# tC-mcu-adapter-rev1.net
KiCad netlist of a schematic drawn in EAGLE
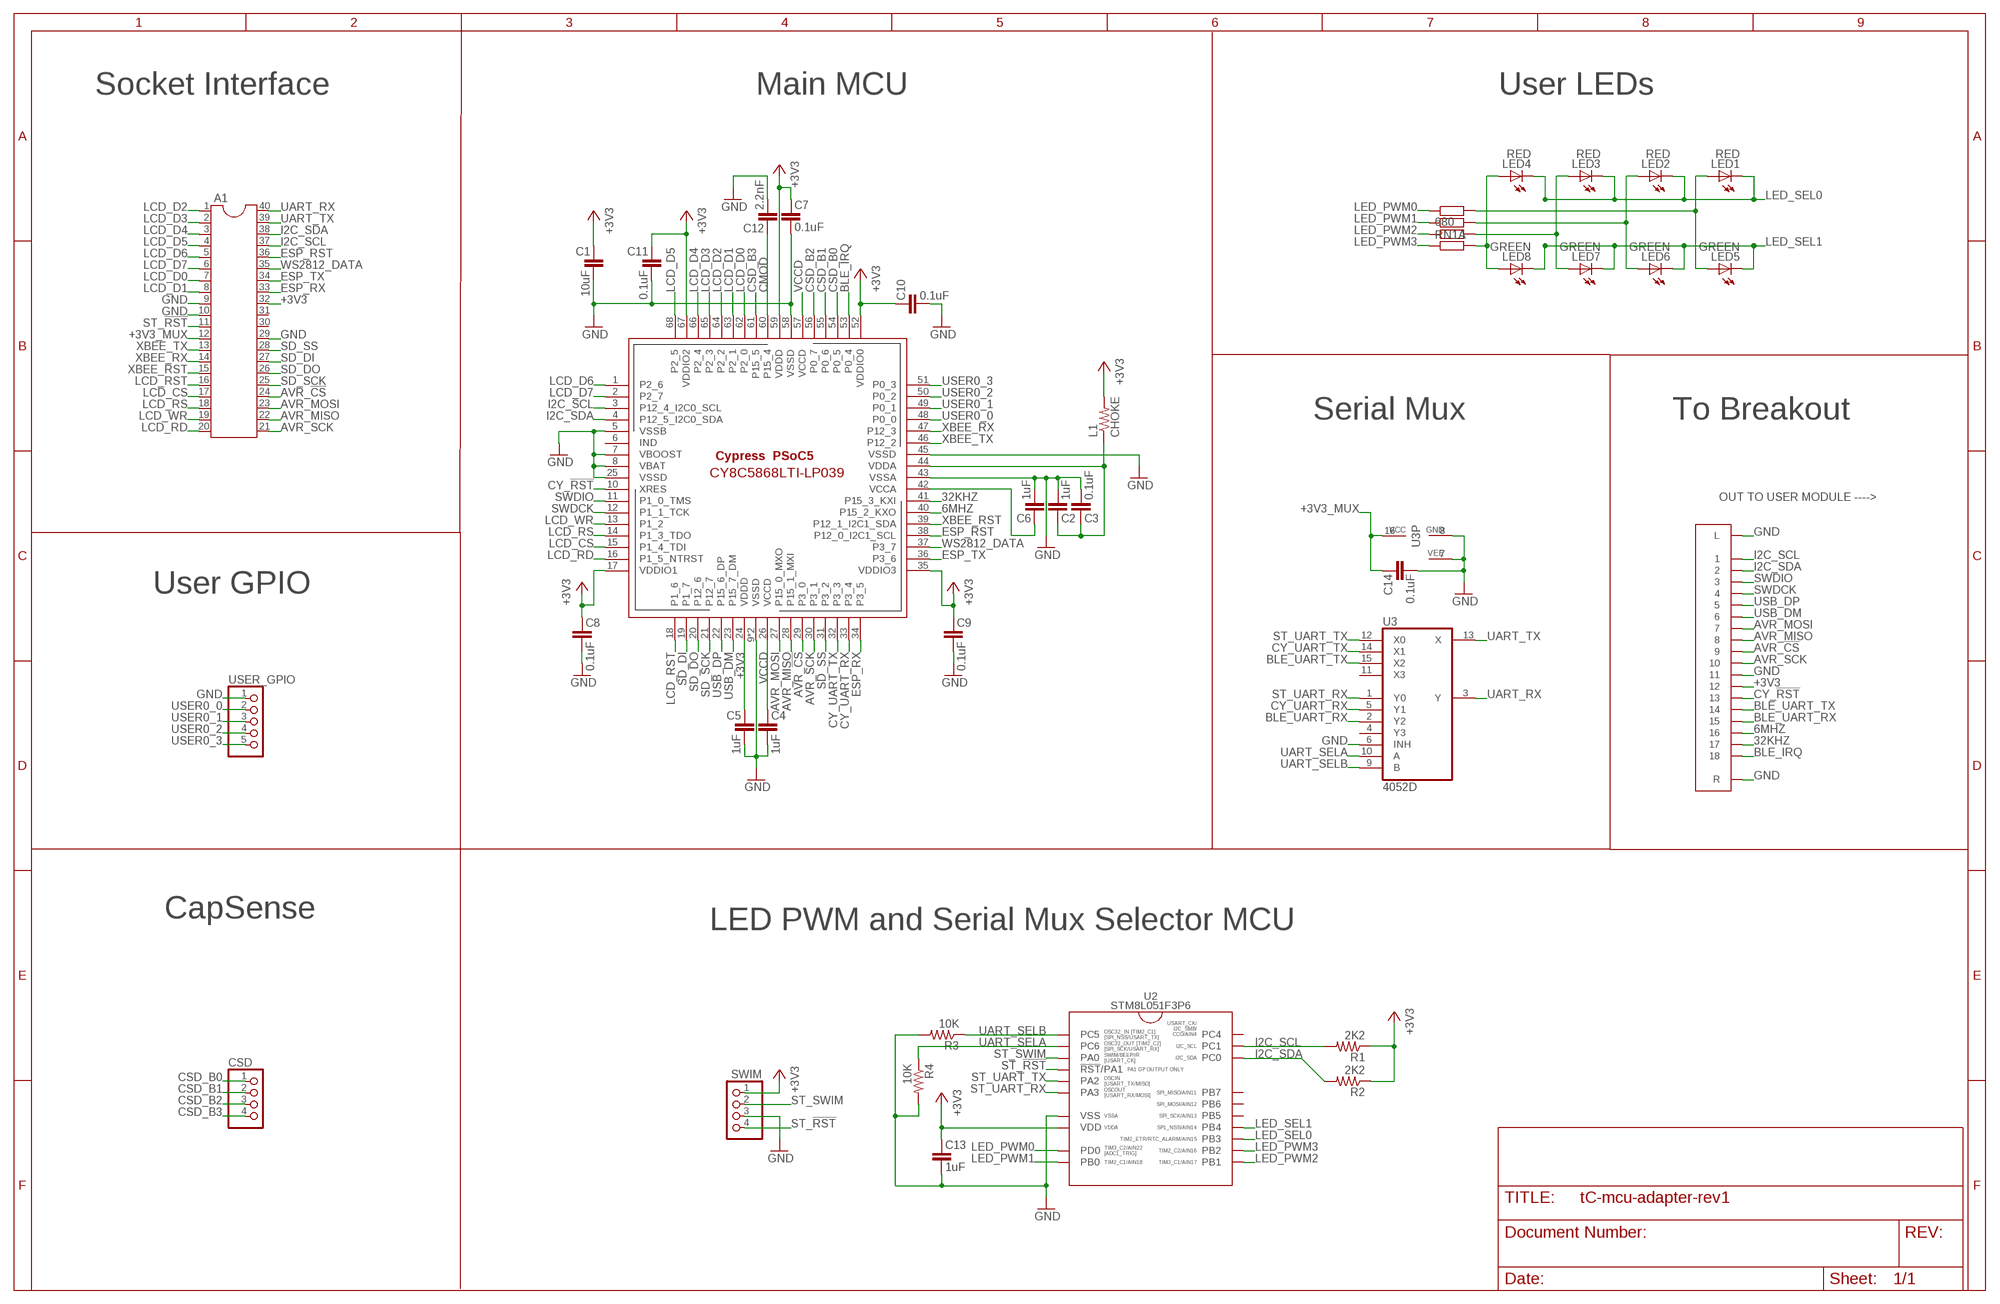
[diagram p0: schematic, sheet 1]

(export (version "E")
  (design (tool "Eeschema 10.0.6"))
  (components
    (comp (ref "A1")
      (value "DIL40")
      (footprint "eagle-import:DIL40")
      (libsource (lib "eagle-import") (part "DIL40"))
    )
    (comp (ref "C1")
      (value "10uF")
      (footprint "eagle-import:C0805K")
      (libsource (lib "eagle-import") (part "C-EUC0805K"))
    )
    (comp (ref "C2")
      (value "1uF")
      (footprint "eagle-import:C0603K")
      (libsource (lib "eagle-import") (part "C-EUC0603K"))
    )
    (comp (ref "C3")
      (value "0.1uF")
      (footprint "eagle-import:C0603K")
      (libsource (lib "eagle-import") (part "C-EUC0603K"))
    )
    (comp (ref "C4")
      (value "1uF")
      (footprint "eagle-import:C0603K")
      (libsource (lib "eagle-import") (part "C-EUC0603K"))
    )
    (comp (ref "C5")
      (value "1uF")
      (footprint "eagle-import:C0603K")
      (libsource (lib "eagle-import") (part "C-EUC0603K"))
    )
    (comp (ref "C6")
      (value "1uF")
      (footprint "eagle-import:C0603K")
      (libsource (lib "eagle-import") (part "C-EUC0603K"))
    )
    (comp (ref "C7")
      (value "0.1uF")
      (footprint "eagle-import:C0603K")
      (libsource (lib "eagle-import") (part "C-EUC0603K"))
    )
    (comp (ref "C8")
      (value "0.1uF")
      (footprint "eagle-import:C0603K")
      (libsource (lib "eagle-import") (part "C-EUC0603K"))
    )
    (comp (ref "C9")
      (value "0.1uF")
      (footprint "eagle-import:C0603K")
      (libsource (lib "eagle-import") (part "C-EUC0603K"))
    )
    (comp (ref "C10")
      (value "0.1uF")
      (footprint "eagle-import:C0603K")
      (libsource (lib "eagle-import") (part "C-EUC0603K"))
    )
    (comp (ref "C11")
      (value "0.1uF")
      (footprint "eagle-import:C0603K")
      (libsource (lib "eagle-import") (part "C-EUC0603K"))
    )
    (comp (ref "C12")
      (value "2.2nF")
      (footprint "eagle-import:C0603K")
      (libsource (lib "eagle-import") (part "C-EUC0603K"))
    )
    (comp (ref "C13")
      (value "1uF")
      (footprint "eagle-import:C0402K")
      (libsource (lib "eagle-import") (part "C-EUC0402K"))
    )
    (comp (ref "C14")
      (value "0.1uF")
      (footprint "eagle-import:C0402K")
      (libsource (lib "eagle-import") (part "C-EUC0402K"))
    )
    (comp (ref "CN1")
      (value "FPC_CONN_18PIN_0.5MM_SMT")
      (footprint "eagle-import:FPC_CONN_18PIN_0.5MM_SMT")
      (libsource (lib "eagle-import") (part "FPC_CONN_18PIN_0.5MM_SMT"))
    )
    (comp (ref "CSD")
      (value "CAP_INTERCONNECT")
      (footprint "eagle-import:CAP_INTERCONNECT")
      (libsource (lib "eagle-import") (part "CAP_INTERCONNECT"))
    )
    (comp (ref "L1")
      (value "CHOKE")
      (footprint "eagle-import:R0805")
      (libsource (lib "eagle-import") (part "R-US_R0805"))
    )
    (comp (ref "LED1")
      (value "RED")
      (footprint "eagle-import:LED-805")
      (libsource (lib "eagle-import") (part "LED-0805"))
    )
    (comp (ref "LED2")
      (value "RED")
      (footprint "eagle-import:LED-805")
      (libsource (lib "eagle-import") (part "LED-0805"))
    )
    (comp (ref "LED3")
      (value "RED")
      (footprint "eagle-import:LED-805")
      (libsource (lib "eagle-import") (part "LED-0805"))
    )
    (comp (ref "LED4")
      (value "RED")
      (footprint "eagle-import:LED-805")
      (libsource (lib "eagle-import") (part "LED-0805"))
    )
    (comp (ref "LED5")
      (value "GREEN")
      (footprint "eagle-import:LED-805")
      (libsource (lib "eagle-import") (part "LED-0805"))
    )
    (comp (ref "LED6")
      (value "GREEN")
      (footprint "eagle-import:LED-805")
      (libsource (lib "eagle-import") (part "LED-0805"))
    )
    (comp (ref "LED7")
      (value "GREEN")
      (footprint "eagle-import:LED-805")
      (libsource (lib "eagle-import") (part "LED-0805"))
    )
    (comp (ref "LED8")
      (value "GREEN")
      (footprint "eagle-import:LED-805")
      (libsource (lib "eagle-import") (part "LED-0805"))
    )
    (comp (ref "R1")
      (value "2K2")
      (footprint "eagle-import:R0603")
      (libsource (lib "eagle-import") (part "R-US_R0603"))
    )
    (comp (ref "R2")
      (value "2K2")
      (footprint "eagle-import:R0603")
      (libsource (lib "eagle-import") (part "R-US_R0603"))
    )
    (comp (ref "R3")
      (value "10K")
      (footprint "eagle-import:R0603")
      (libsource (lib "eagle-import") (part "R-US_R0603"))
    )
    (comp (ref "R4")
      (value "10K")
      (footprint "eagle-import:R0603")
      (libsource (lib "eagle-import") (part "R-US_R0603"))
    )
    (comp (ref "RN1")
      (value "680")
      (footprint "eagle-import:RN8P-4R-CRA06S")
      (libsource (lib "eagle-import") (part "RESISTOR_ARRAY_4"))
    )
    (comp (ref "SWIM")
      (value "PINHD-1X4")
      (footprint "eagle-import:1X04")
      (libsource (lib "eagle-import") (part "PINHD-1X4"))
    )
    (comp (ref "U1")
      (value "CY8C5XXX-68-N")
      (footprint "eagle-import:QFN68N")
      (libsource (lib "eagle-import") (part "CY8C5XXX-68-N"))
    )
    (comp (ref "U2")
      (value "STM8L051F3P6")
      (footprint "eagle-import:TSSOP20")
      (libsource (lib "eagle-import") (part "STM8L051F3P6"))
    )
    (comp (ref "U3")
      (value "4052D")
      (footprint "eagle-import:SO16")
      (libsource (lib "eagle-import") (part "4052D"))
    )
    (comp (ref "USER_GPIO")
      (value "PINHD-1X5/90")
      (footprint "eagle-import:1X05_90")
      (libsource (lib "eagle-import") (part "PINHD-1X5/90"))
    )
  )
  (nets
    (net (code "1") (name "+3V3") (class "Default")
      (node (ref "A1") (pin "32") (pinfunction "32_32") (pintype "passive"))
      (node (ref "C1") (pin "1") (pinfunction "1_1") (pintype "passive"))
      (node (ref "C10") (pin "1") (pinfunction "1_1") (pintype "passive"))
      (node (ref "C11") (pin "1") (pinfunction "1_1") (pintype "passive"))
      (node (ref "C13") (pin "1") (pinfunction "1_1") (pintype "passive"))
      (node (ref "C5") (pin "1") (pinfunction "1_1") (pintype "passive"))
      (node (ref "C7") (pin "1") (pinfunction "1_1") (pintype "passive"))
      (node (ref "C8") (pin "1") (pinfunction "1_1") (pintype "passive"))
      (node (ref "C9") (pin "1") (pinfunction "1_1") (pintype "passive"))
      (node (ref "CN1") (pin "12") (pinfunction "12_12") (pintype "bidirectional"))
      (node (ref "L1") (pin "2") (pinfunction "2_2") (pintype "passive"))
      (node (ref "R1") (pin "1") (pinfunction "1_1") (pintype "passive"))
      (node (ref "R2") (pin "1") (pinfunction "1_1") (pintype "passive"))
      (node (ref "SWIM") (pin "1") (pinfunction "1_1") (pintype "passive"))
      (node (ref "U1") (pin "17") (pinfunction "VDDIO1_17") (pintype "passive"))
      (node (ref "U1") (pin "24") (pinfunction "VDDD_24") (pintype "passive"))
      (node (ref "U1") (pin "35") (pinfunction "VDDIO3_35") (pintype "passive"))
      (node (ref "U1") (pin "52") (pinfunction "VDDIO0_52") (pintype "passive"))
      (node (ref "U1") (pin "59") (pinfunction "VDDD_59") (pintype "passive"))
      (node (ref "U1") (pin "67") (pinfunction "VDDIO2_67") (pintype "passive"))
      (node (ref "U2") (pin "8") (pinfunction "VDD_8") (pintype "bidirectional"))
    )
    (net (code "2") (name "/+3V3_MUX") (class "Default")
      (node (ref "A1") (pin "12") (pinfunction "12_12") (pintype "passive"))
      (node (ref "C14") (pin "1") (pinfunction "1_1") (pintype "passive"))
      (node (ref "U3") (pin "16") (pinfunction "VCC_16") (pintype "power_in"))
    )
    (net (code "3") (name "/6MHZ") (class "Default")
      (node (ref "CN1") (pin "16") (pinfunction "16_16") (pintype "bidirectional"))
      (node (ref "U1") (pin "40") (pinfunction "P15_2_KXO_40") (pintype "passive"))
    )
    (net (code "4") (name "/32KHZ") (class "Default")
      (node (ref "CN1") (pin "17") (pinfunction "17_17") (pintype "bidirectional"))
      (node (ref "U1") (pin "41") (pinfunction "P15_3_KXI_41") (pintype "passive"))
    )
    (net (code "5") (name "/AVR_MISO") (class "Default")
      (node (ref "A1") (pin "22") (pinfunction "22_22") (pintype "passive"))
      (node (ref "CN1") (pin "8") (pinfunction "8_8") (pintype "bidirectional"))
      (node (ref "U1") (pin "28") (pinfunction "P15_1_MXI_28") (pintype "passive"))
    )
    (net (code "6") (name "/AVR_MOSI") (class "Default")
      (node (ref "A1") (pin "23") (pinfunction "23_23") (pintype "passive"))
      (node (ref "CN1") (pin "7") (pinfunction "7_7") (pintype "bidirectional"))
      (node (ref "U1") (pin "27") (pinfunction "P15_0_MXO_27") (pintype "passive"))
    )
    (net (code "7") (name "/AVR_SCK") (class "Default")
      (node (ref "A1") (pin "21") (pinfunction "21_21") (pintype "passive"))
      (node (ref "CN1") (pin "10") (pinfunction "10_10") (pintype "bidirectional"))
      (node (ref "U1") (pin "30") (pinfunction "P3_1_30") (pintype "passive"))
    )
    (net (code "8") (name "/AVR_~{CS}") (class "Default")
      (node (ref "A1") (pin "24") (pinfunction "24_24") (pintype "passive"))
      (node (ref "CN1") (pin "9") (pinfunction "9_9") (pintype "bidirectional"))
      (node (ref "U1") (pin "29") (pinfunction "P3_0_29") (pintype "passive"))
    )
    (net (code "9") (name "/BLE_IRQ") (class "Default")
      (node (ref "CN1") (pin "18") (pinfunction "18_18") (pintype "bidirectional"))
      (node (ref "U1") (pin "53") (pinfunction "P0_4_53") (pintype "passive"))
    )
    (net (code "10") (name "/BLE_UART_RX") (class "Default")
      (node (ref "CN1") (pin "15") (pinfunction "15_15") (pintype "bidirectional"))
      (node (ref "U3") (pin "2") (pinfunction "Y2_2") (pintype "bidirectional"))
    )
    (net (code "11") (name "/BLE_UART_TX") (class "Default")
      (node (ref "CN1") (pin "14") (pinfunction "14_14") (pintype "bidirectional"))
      (node (ref "U3") (pin "15") (pinfunction "X2_15") (pintype "bidirectional"))
    )
    (net (code "12") (name "/CMOD") (class "Default")
      (node (ref "C12") (pin "1") (pinfunction "1_1") (pintype "passive"))
      (node (ref "U1") (pin "60") (pinfunction "P15_4_60") (pintype "passive"))
    )
    (net (code "13") (name "/CSD_B0") (class "Default")
      (node (ref "CSD") (pin "1") (pinfunction "1_1") (pintype "passive"))
      (node (ref "U1") (pin "54") (pinfunction "P0_5_54") (pintype "passive"))
    )
    (net (code "14") (name "/CSD_B1") (class "Default")
      (node (ref "CSD") (pin "2") (pinfunction "2_2") (pintype "passive"))
      (node (ref "U1") (pin "55") (pinfunction "P0_6_55") (pintype "passive"))
    )
    (net (code "15") (name "/CSD_B2") (class "Default")
      (node (ref "CSD") (pin "3") (pinfunction "3_3") (pintype "passive"))
      (node (ref "U1") (pin "56") (pinfunction "P0_7_56") (pintype "passive"))
    )
    (net (code "16") (name "/CSD_B3") (class "Default")
      (node (ref "CSD") (pin "4") (pinfunction "4_4") (pintype "passive"))
      (node (ref "U1") (pin "61") (pinfunction "P15_5_61") (pintype "passive"))
    )
    (net (code "17") (name "/CY_UART_RX") (class "Default")
      (node (ref "U1") (pin "33") (pinfunction "P3_4_33") (pintype "passive"))
      (node (ref "U3") (pin "5") (pinfunction "Y1_5") (pintype "bidirectional"))
    )
    (net (code "18") (name "/CY_UART_TX") (class "Default")
      (node (ref "U1") (pin "32") (pinfunction "P3_3_32") (pintype "passive"))
      (node (ref "U3") (pin "14") (pinfunction "X1_14") (pintype "bidirectional"))
    )
    (net (code "19") (name "/CY_~{RST}") (class "Default")
      (node (ref "CN1") (pin "13") (pinfunction "13_13") (pintype "bidirectional"))
      (node (ref "U1") (pin "10") (pinfunction "XRES_10") (pintype "passive"))
    )
    (net (code "20") (name "/ESP_RST") (class "Default")
      (node (ref "A1") (pin "36") (pinfunction "36_36") (pintype "passive"))
      (node (ref "U1") (pin "38") (pinfunction "P12_0_I2C1_SCL_38") (pintype "passive"))
    )
    (net (code "21") (name "/ESP_RX") (class "Default")
      (node (ref "A1") (pin "33") (pinfunction "33_33") (pintype "passive"))
      (node (ref "U1") (pin "34") (pinfunction "P3_5_34") (pintype "passive"))
    )
    (net (code "22") (name "/ESP_TX") (class "Default")
      (node (ref "A1") (pin "34") (pinfunction "34_34") (pintype "passive"))
      (node (ref "U1") (pin "36") (pinfunction "P3_6_36") (pintype "passive"))
    )
    (net (code "23") (name "/I2C_SCL") (class "Default")
      (node (ref "A1") (pin "37") (pinfunction "37_37") (pintype "passive"))
      (node (ref "CN1") (pin "1") (pinfunction "1_1") (pintype "bidirectional"))
      (node (ref "R1") (pin "2") (pinfunction "2_2") (pintype "passive"))
      (node (ref "U1") (pin "3") (pinfunction "P12_4_I2C0_SCL_3") (pintype "passive"))
      (node (ref "U2") (pin "19") (pinfunction "PC1_19") (pintype "bidirectional"))
    )
    (net (code "24") (name "/I2C_SDA") (class "Default")
      (node (ref "A1") (pin "38") (pinfunction "38_38") (pintype "passive"))
      (node (ref "CN1") (pin "2") (pinfunction "2_2") (pintype "bidirectional"))
      (node (ref "R2") (pin "2") (pinfunction "2_2") (pintype "passive"))
      (node (ref "U1") (pin "4") (pinfunction "P12_5_I2C0_SDA_4") (pintype "passive"))
      (node (ref "U2") (pin "18") (pinfunction "PC0_18") (pintype "bidirectional"))
    )
    (net (code "25") (name "/LCD_CS") (class "Default")
      (node (ref "A1") (pin "17") (pinfunction "17_17") (pintype "passive"))
      (node (ref "U1") (pin "15") (pinfunction "P1_4_TDI_15") (pintype "passive"))
    )
    (net (code "26") (name "/LCD_D0") (class "Default")
      (node (ref "A1") (pin "7") (pinfunction "7_7") (pintype "passive"))
      (node (ref "U1") (pin "62") (pinfunction "P2_0_62") (pintype "passive"))
    )
    (net (code "27") (name "/LCD_D1") (class "Default")
      (node (ref "A1") (pin "8") (pinfunction "8_8") (pintype "passive"))
      (node (ref "U1") (pin "63") (pinfunction "P2_1_63") (pintype "passive"))
    )
    (net (code "28") (name "/LCD_D2") (class "Default")
      (node (ref "A1") (pin "1") (pinfunction "1_1") (pintype "passive"))
      (node (ref "U1") (pin "64") (pinfunction "P2_2_64") (pintype "passive"))
    )
    (net (code "29") (name "/LCD_D3") (class "Default")
      (node (ref "A1") (pin "2") (pinfunction "2_2") (pintype "passive"))
      (node (ref "U1") (pin "65") (pinfunction "P2_3_65") (pintype "passive"))
    )
    (net (code "30") (name "/LCD_D4") (class "Default")
      (node (ref "A1") (pin "3") (pinfunction "3_3") (pintype "passive"))
      (node (ref "U1") (pin "66") (pinfunction "P2_4_66") (pintype "passive"))
    )
    (net (code "31") (name "/LCD_D5") (class "Default")
      (node (ref "A1") (pin "4") (pinfunction "4_4") (pintype "passive"))
      (node (ref "U1") (pin "68") (pinfunction "P2_5_68") (pintype "passive"))
    )
    (net (code "32") (name "/LCD_D6") (class "Default")
      (node (ref "A1") (pin "5") (pinfunction "5_5") (pintype "passive"))
      (node (ref "U1") (pin "1") (pinfunction "P2_6_1") (pintype "passive"))
    )
    (net (code "33") (name "/LCD_D7") (class "Default")
      (node (ref "A1") (pin "6") (pinfunction "6_6") (pintype "passive"))
      (node (ref "U1") (pin "2") (pinfunction "P2_7_2") (pintype "passive"))
    )
    (net (code "34") (name "/LCD_RD") (class "Default")
      (node (ref "A1") (pin "20") (pinfunction "20_20") (pintype "passive"))
      (node (ref "U1") (pin "16") (pinfunction "P1_5_NTRST_16") (pintype "passive"))
    )
    (net (code "35") (name "/LCD_RS") (class "Default")
      (node (ref "A1") (pin "18") (pinfunction "18_18") (pintype "passive"))
      (node (ref "U1") (pin "14") (pinfunction "P1_3_TDO_14") (pintype "passive"))
    )
    (net (code "36") (name "/LCD_RST") (class "Default")
      (node (ref "A1") (pin "16") (pinfunction "16_16") (pintype "passive"))
      (node (ref "U1") (pin "18") (pinfunction "P1_6_18") (pintype "passive"))
    )
    (net (code "37") (name "/LCD_WR") (class "Default")
      (node (ref "A1") (pin "19") (pinfunction "19_19") (pintype "passive"))
      (node (ref "U1") (pin "13") (pinfunction "P1_2_13") (pintype "passive"))
    )
    (net (code "38") (name "/LED_PWM0") (class "Default")
      (node (ref "RN1") (pin "4") (pinfunction "1_4") (pintype "passive"))
      (node (ref "U2") (pin "9") (pinfunction "PD0_9") (pintype "bidirectional"))
    )
    (net (code "39") (name "/LED_PWM1") (class "Default")
      (node (ref "RN1") (pin "3") (pinfunction "1_3") (pintype "passive"))
      (node (ref "U2") (pin "10") (pinfunction "PB0_10") (pintype "bidirectional"))
    )
    (net (code "40") (name "/LED_PWM2") (class "Default")
      (node (ref "RN1") (pin "2") (pinfunction "1_2") (pintype "passive"))
      (node (ref "U2") (pin "11") (pinfunction "PB1_11") (pintype "bidirectional"))
    )
    (net (code "41") (name "/LED_PWM3") (class "Default")
      (node (ref "RN1") (pin "1") (pinfunction "1_1") (pintype "passive"))
      (node (ref "U2") (pin "12") (pinfunction "PB2_12") (pintype "bidirectional"))
    )
    (net (code "42") (name "/LED_SEL0") (class "Default")
      (node (ref "LED1") (pin "C") (pinfunction "C_C") (pintype "passive"))
      (node (ref "LED2") (pin "C") (pinfunction "C_C") (pintype "passive"))
      (node (ref "LED3") (pin "C") (pinfunction "C_C") (pintype "passive"))
      (node (ref "LED4") (pin "C") (pinfunction "C_C") (pintype "passive"))
      (node (ref "U2") (pin "13") (pinfunction "PB3_13") (pintype "bidirectional"))
    )
    (net (code "43") (name "/LED_SEL1") (class "Default")
      (node (ref "LED5") (pin "C") (pinfunction "C_C") (pintype "passive"))
      (node (ref "LED6") (pin "C") (pinfunction "C_C") (pintype "passive"))
      (node (ref "LED7") (pin "C") (pinfunction "C_C") (pintype "passive"))
      (node (ref "LED8") (pin "C") (pinfunction "C_C") (pintype "passive"))
      (node (ref "U2") (pin "14") (pinfunction "PB4_14") (pintype "bidirectional"))
    )
    (net (code "44") (name "/SD_DI") (class "Default")
      (node (ref "A1") (pin "27") (pinfunction "27_27") (pintype "passive"))
      (node (ref "U1") (pin "19") (pinfunction "P1_7_19") (pintype "passive"))
    )
    (net (code "45") (name "/SD_DO") (class "Default")
      (node (ref "A1") (pin "26") (pinfunction "26_26") (pintype "passive"))
      (node (ref "U1") (pin "20") (pinfunction "P12_6_20") (pintype "passive"))
    )
    (net (code "46") (name "/SD_SCK") (class "Default")
      (node (ref "A1") (pin "25") (pinfunction "25_25") (pintype "passive"))
      (node (ref "U1") (pin "21") (pinfunction "P12_7_21") (pintype "passive"))
    )
    (net (code "47") (name "/SD_SS") (class "Default")
      (node (ref "A1") (pin "28") (pinfunction "28_28") (pintype "passive"))
      (node (ref "U1") (pin "31") (pinfunction "P3_2_31") (pintype "passive"))
    )
    (net (code "48") (name "/ST_SWIM") (class "Default")
      (node (ref "SWIM") (pin "2") (pinfunction "2_2") (pintype "passive"))
      (node (ref "U2") (pin "3") (pinfunction "PA0_3") (pintype "bidirectional"))
    )
    (net (code "49") (name "/ST_UART_RX") (class "Default")
      (node (ref "U2") (pin "6") (pinfunction "PA3_6") (pintype "bidirectional"))
      (node (ref "U3") (pin "1") (pinfunction "Y0_1") (pintype "bidirectional"))
    )
    (net (code "50") (name "/ST_UART_TX") (class "Default")
      (node (ref "U2") (pin "5") (pinfunction "PA2_5") (pintype "bidirectional"))
      (node (ref "U3") (pin "12") (pinfunction "X0_12") (pintype "bidirectional"))
    )
    (net (code "51") (name "/ST_~{RST}") (class "Default")
      (node (ref "A1") (pin "11") (pinfunction "11_11") (pintype "passive"))
      (node (ref "SWIM") (pin "4") (pinfunction "4_4") (pintype "passive"))
      (node (ref "U2") (pin "4") (pinfunction "~{RST}/PA1_4") (pintype "bidirectional"))
    )
    (net (code "52") (name "/SWDCK") (class "Default")
      (node (ref "CN1") (pin "4") (pinfunction "4_4") (pintype "bidirectional"))
      (node (ref "U1") (pin "12") (pinfunction "P1_1_TCK_12") (pintype "passive"))
    )
    (net (code "53") (name "/SWDIO") (class "Default")
      (node (ref "CN1") (pin "3") (pinfunction "3_3") (pintype "bidirectional"))
      (node (ref "U1") (pin "11") (pinfunction "P1_0_TMS_11") (pintype "passive"))
    )
    (net (code "54") (name "/UART_RX") (class "Default")
      (node (ref "A1") (pin "40") (pinfunction "40_40") (pintype "passive"))
      (node (ref "U3") (pin "3") (pinfunction "Y_3") (pintype "bidirectional"))
    )
    (net (code "55") (name "/UART_SELA") (class "Default")
      (node (ref "R4") (pin "1") (pinfunction "1_1") (pintype "passive"))
      (node (ref "U2") (pin "2") (pinfunction "PC6_2") (pintype "bidirectional"))
      (node (ref "U3") (pin "10") (pinfunction "A_10") (pintype "input"))
    )
    (net (code "56") (name "/UART_SELB") (class "Default")
      (node (ref "R3") (pin "1") (pinfunction "1_1") (pintype "passive"))
      (node (ref "U2") (pin "1") (pinfunction "PC5_1") (pintype "bidirectional"))
      (node (ref "U3") (pin "9") (pinfunction "B_9") (pintype "input"))
    )
    (net (code "57") (name "/UART_TX") (class "Default")
      (node (ref "A1") (pin "39") (pinfunction "39_39") (pintype "passive"))
      (node (ref "U3") (pin "13") (pinfunction "X_13") (pintype "bidirectional"))
    )
    (net (code "58") (name "/USB_DM") (class "Default")
      (node (ref "CN1") (pin "6") (pinfunction "6_6") (pintype "bidirectional"))
      (node (ref "U1") (pin "23") (pinfunction "P15_7_DM_23") (pintype "passive"))
    )
    (net (code "59") (name "/USB_DP") (class "Default")
      (node (ref "CN1") (pin "5") (pinfunction "5_5") (pintype "bidirectional"))
      (node (ref "U1") (pin "22") (pinfunction "P15_6_DP_22") (pintype "passive"))
    )
    (net (code "60") (name "/USER0_0") (class "Default")
      (node (ref "U1") (pin "48") (pinfunction "P0_0_48") (pintype "passive"))
      (node (ref "USER_GPIO") (pin "2") (pinfunction "2_2") (pintype "passive"))
    )
    (net (code "61") (name "/USER0_1") (class "Default")
      (node (ref "U1") (pin "49") (pinfunction "P0_1_49") (pintype "passive"))
      (node (ref "USER_GPIO") (pin "3") (pinfunction "3_3") (pintype "passive"))
    )
    (net (code "62") (name "/USER0_2") (class "Default")
      (node (ref "U1") (pin "50") (pinfunction "P0_2_50") (pintype "passive"))
      (node (ref "USER_GPIO") (pin "4") (pinfunction "4_4") (pintype "passive"))
    )
    (net (code "63") (name "/USER0_3") (class "Default")
      (node (ref "U1") (pin "51") (pinfunction "P0_3_51") (pintype "passive"))
      (node (ref "USER_GPIO") (pin "5") (pinfunction "5_5") (pintype "passive"))
    )
    (net (code "64") (name "/VCCD") (class "Default")
      (node (ref "C4") (pin "1") (pinfunction "1_1") (pintype "passive"))
      (node (ref "U1") (pin "26") (pinfunction "VCCD_26") (pintype "passive"))
      (node (ref "U1") (pin "57") (pinfunction "VCCD_57") (pintype "passive"))
    )
    (net (code "65") (name "/WS2812_DATA") (class "Default")
      (node (ref "A1") (pin "35") (pinfunction "35_35") (pintype "passive"))
      (node (ref "U1") (pin "37") (pinfunction "P3_7_37") (pintype "passive"))
    )
    (net (code "66") (name "/XBEE_RST") (class "Default")
      (node (ref "A1") (pin "15") (pinfunction "15_15") (pintype "passive"))
      (node (ref "U1") (pin "39") (pinfunction "P12_1_I2C1_SDA_39") (pintype "passive"))
    )
    (net (code "67") (name "/XBEE_RX") (class "Default")
      (node (ref "A1") (pin "14") (pinfunction "14_14") (pintype "passive"))
      (node (ref "U1") (pin "47") (pinfunction "P12_3_47") (pintype "passive"))
    )
    (net (code "68") (name "/XBEE_TX") (class "Default")
      (node (ref "A1") (pin "13") (pinfunction "13_13") (pintype "passive"))
      (node (ref "U1") (pin "46") (pinfunction "P12_2_46") (pintype "passive"))
    )
    (net (code "69") (name "GND") (class "Default")
      (node (ref "A1") (pin "10") (pinfunction "10_10") (pintype "passive"))
      (node (ref "A1") (pin "29") (pinfunction "29_29") (pintype "passive"))
      (node (ref "A1") (pin "9") (pinfunction "9_9") (pintype "passive"))
      (node (ref "C1") (pin "2") (pinfunction "2_2") (pintype "passive"))
      (node (ref "C10") (pin "2") (pinfunction "2_2") (pintype "passive"))
      (node (ref "C11") (pin "2") (pinfunction "2_2") (pintype "passive"))
      (node (ref "C12") (pin "2") (pinfunction "2_2") (pintype "passive"))
      (node (ref "C13") (pin "2") (pinfunction "2_2") (pintype "passive"))
      (node (ref "C14") (pin "2") (pinfunction "2_2") (pintype "passive"))
      (node (ref "C2") (pin "2") (pinfunction "2_2") (pintype "passive"))
      (node (ref "C3") (pin "2") (pinfunction "2_2") (pintype "passive"))
      (node (ref "C4") (pin "2") (pinfunction "2_2") (pintype "passive"))
      (node (ref "C5") (pin "2") (pinfunction "2_2") (pintype "passive"))
      (node (ref "C6") (pin "2") (pinfunction "2_2") (pintype "passive"))
      (node (ref "C7") (pin "2") (pinfunction "2_2") (pintype "passive"))
      (node (ref "C8") (pin "2") (pinfunction "2_2") (pintype "passive"))
      (node (ref "C9") (pin "2") (pinfunction "2_2") (pintype "passive"))
      (node (ref "CN1") (pin "11") (pinfunction "11_11") (pintype "bidirectional"))
      (node (ref "CN1") (pin "GL") (pinfunction "L_GL") (pintype "bidirectional"))
      (node (ref "CN1") (pin "GR") (pinfunction "R_GR") (pintype "bidirectional"))
      (node (ref "R3") (pin "2") (pinfunction "2_2") (pintype "passive"))
      (node (ref "R4") (pin "2") (pinfunction "2_2") (pintype "passive"))
      (node (ref "SWIM") (pin "3") (pinfunction "3_3") (pintype "passive"))
      (node (ref "U1") (pin "25") (pinfunction "VSSD_25") (pintype "passive"))
      (node (ref "U1") (pin "43") (pinfunction "VSSA_43") (pintype "passive"))
      (node (ref "U1") (pin "45") (pinfunction "VSSD_45") (pintype "passive"))
      (node (ref "U1") (pin "5") (pinfunction "VSSB_5") (pintype "passive"))
      (node (ref "U1") (pin "58") (pinfunction "VSSD_58") (pintype "passive"))
      (node (ref "U1") (pin "7") (pinfunction "VBOOST_7") (pintype "passive"))
      (node (ref "U1") (pin "8") (pinfunction "VBAT_8") (pintype "passive"))
      (node (ref "U1") (pin "9") (pinfunction "VSSD_9") (pintype "passive"))
      (node (ref "U1") (pin "EPAD") (pinfunction "VSSD_EPAD") (pintype "passive"))
      (node (ref "U2") (pin "7") (pinfunction "VSS_7") (pintype "bidirectional"))
      (node (ref "U3") (pin "6") (pinfunction "INH_6") (pintype "input"))
      (node (ref "U3") (pin "7") (pinfunction "VEE_7") (pintype "power_in"))
      (node (ref "U3") (pin "8") (pinfunction "GND_8") (pintype "power_in"))
      (node (ref "USER_GPIO") (pin "1") (pinfunction "1_1") (pintype "passive"))
    )
    (net (code "70") (name "Net-(RN1A-2)") (class "Default")
      (node (ref "LED4") (pin "A") (pinfunction "A_A") (pintype "passive"))
      (node (ref "LED8") (pin "A") (pinfunction "A_A") (pintype "passive"))
      (node (ref "RN1") (pin "8") (pinfunction "2_8") (pintype "passive"))
    )
    (net (code "71") (name "Net-(RN1B-2)") (class "Default")
      (node (ref "LED3") (pin "A") (pinfunction "A_A") (pintype "passive"))
      (node (ref "LED7") (pin "A") (pinfunction "A_A") (pintype "passive"))
      (node (ref "RN1") (pin "7") (pinfunction "2_7") (pintype "passive"))
    )
    (net (code "72") (name "Net-(RN1C-2)") (class "Default")
      (node (ref "LED2") (pin "A") (pinfunction "A_A") (pintype "passive"))
      (node (ref "LED6") (pin "A") (pinfunction "A_A") (pintype "passive"))
      (node (ref "RN1") (pin "6") (pinfunction "2_6") (pintype "passive"))
    )
    (net (code "73") (name "Net-(RN1D-2)") (class "Default")
      (node (ref "LED1") (pin "A") (pinfunction "A_A") (pintype "passive"))
      (node (ref "LED5") (pin "A") (pinfunction "A_A") (pintype "passive"))
      (node (ref "RN1") (pin "5") (pinfunction "2_5") (pintype "passive"))
    )
    (net (code "74") (name "Net-(U1-VCCA)") (class "Default")
      (node (ref "C6") (pin "1") (pinfunction "1_1") (pintype "passive"))
      (node (ref "U1") (pin "42") (pinfunction "VCCA_42") (pintype "passive"))
    )
    (net (code "75") (name "Net-(U1-VDDA)") (class "Default")
      (node (ref "C2") (pin "1") (pinfunction "1_1") (pintype "passive"))
      (node (ref "C3") (pin "1") (pinfunction "1_1") (pintype "passive"))
      (node (ref "L1") (pin "1") (pinfunction "1_1") (pintype "passive"))
      (node (ref "U1") (pin "44") (pinfunction "VDDA_44") (pintype "passive"))
    )
    (net (code "76") (name "unconnected-(A1-Pad30)") (class "Default")
      (node (ref "A1") (pin "30") (pinfunction "30_30") (pintype "passive"))
    )
    (net (code "77") (name "unconnected-(A1-Pad31)") (class "Default")
      (node (ref "A1") (pin "31") (pinfunction "31_31") (pintype "passive"))
    )
    (net (code "78") (name "unconnected-(U1-IND-Pad6)") (class "Default")
      (node (ref "U1") (pin "6") (pinfunction "IND_6") (pintype "passive"))
    )
    (net (code "79") (name "unconnected-(U2-PB5-Pad15)") (class "Default")
      (node (ref "U2") (pin "15") (pinfunction "PB5_15") (pintype "bidirectional"))
    )
    (net (code "80") (name "unconnected-(U2-PB6-Pad16)") (class "Default")
      (node (ref "U2") (pin "16") (pinfunction "PB6_16") (pintype "bidirectional"))
    )
    (net (code "81") (name "unconnected-(U2-PB7-Pad17)") (class "Default")
      (node (ref "U2") (pin "17") (pinfunction "PB7_17") (pintype "bidirectional"))
    )
    (net (code "82") (name "unconnected-(U2-PC4-Pad20)") (class "Default")
      (node (ref "U2") (pin "20") (pinfunction "PC4_20") (pintype "bidirectional"))
    )
    (net (code "83") (name "unconnected-(U3A-X3-Pad11)") (class "Default")
      (node (ref "U3") (pin "11") (pinfunction "X3_11") (pintype "bidirectional"))
    )
    (net (code "84") (name "unconnected-(U3A-Y3-Pad4)") (class "Default")
      (node (ref "U3") (pin "4") (pinfunction "Y3_4") (pintype "bidirectional"))
    )
  )
)
